# sensing_unit_rev3.net
KiCad netlist of a schematic drawn in EAGLE
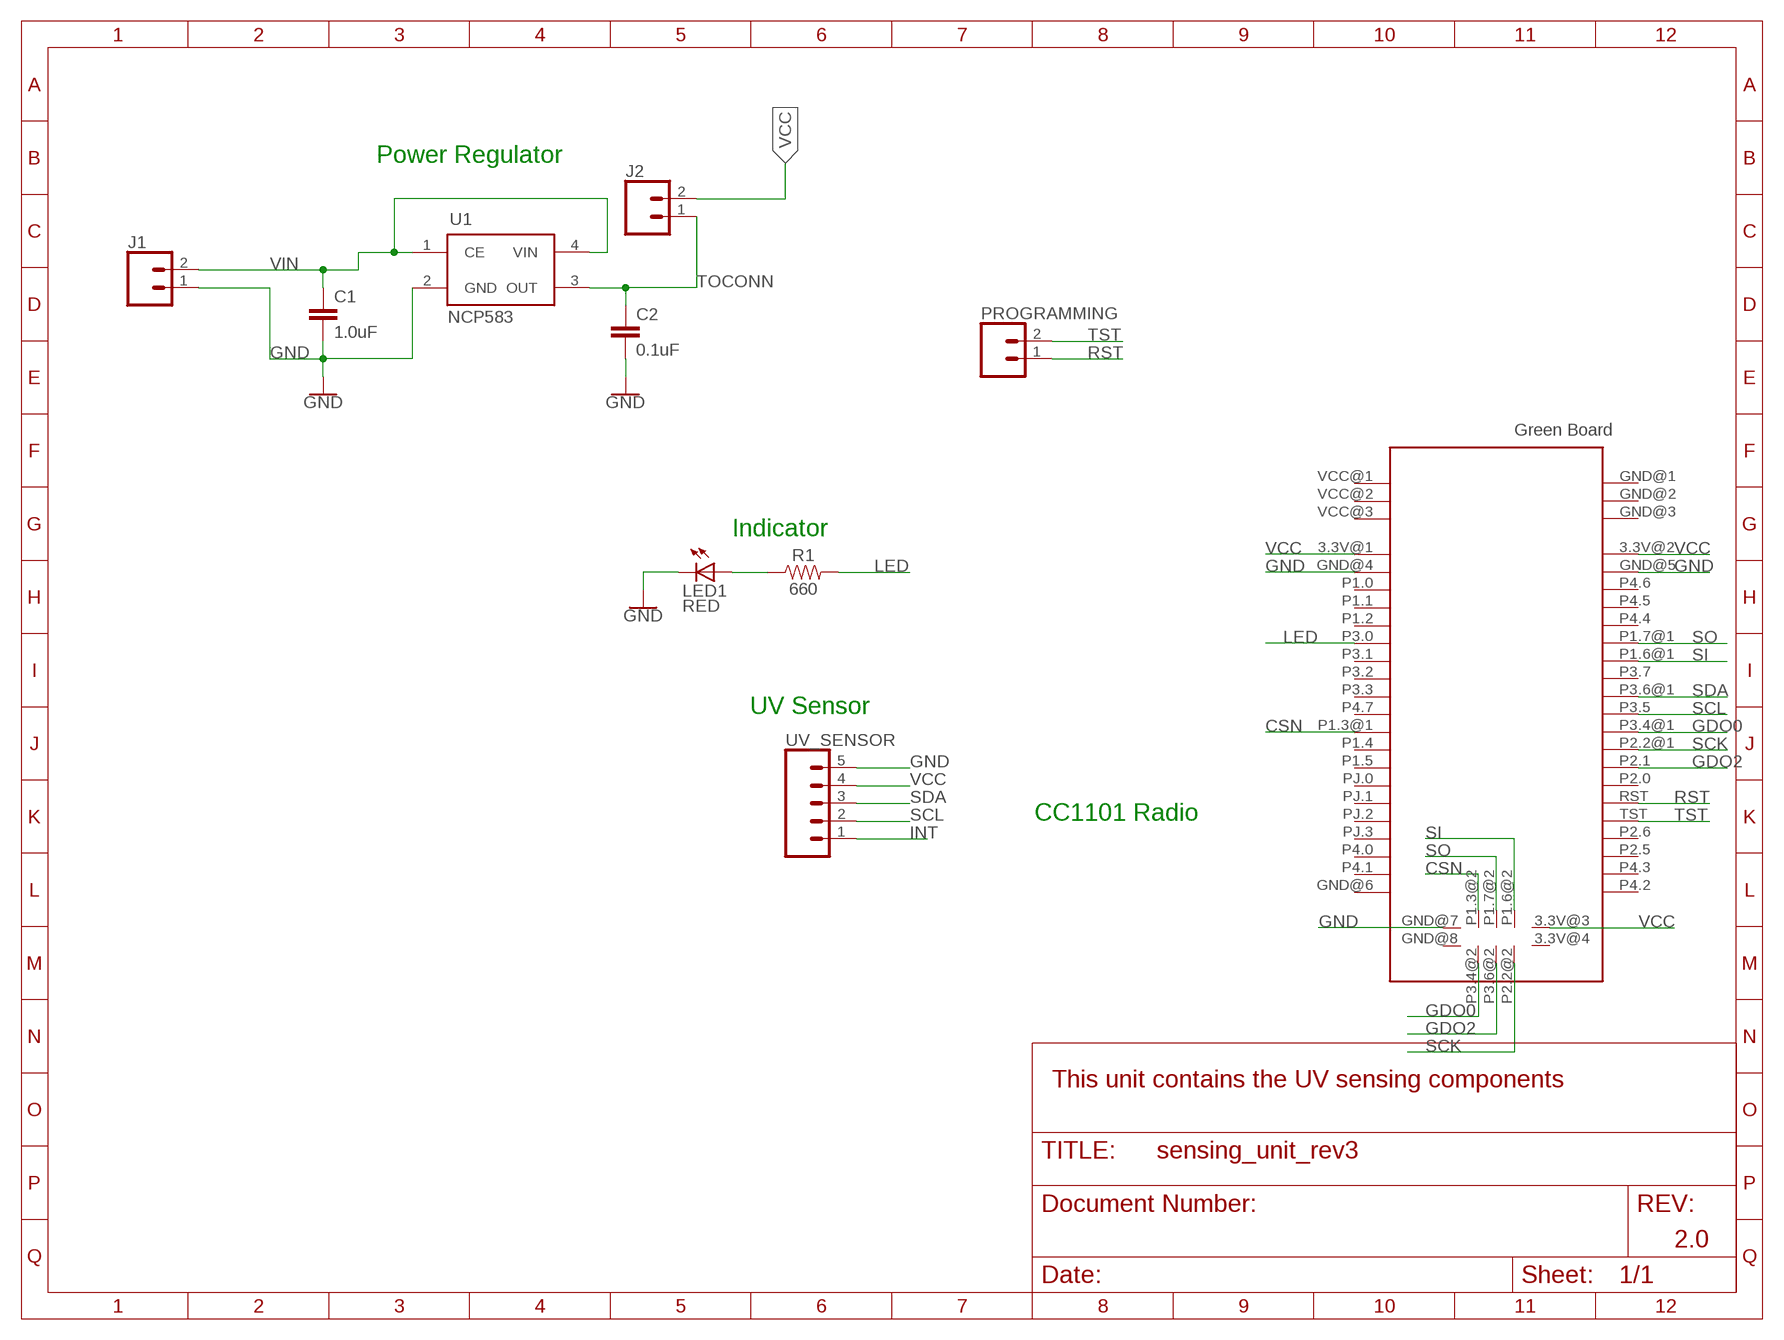
[diagram p0: schematic, sheet 1]

(export (version "E")
  (design (tool "Eeschema 10.0.6"))
  (components
    (comp (ref "C1")
      (value "1.0uF")
      (footprint "eagle-import:0805")
      (libsource (lib "eagle-import") (part "1.0UF-0805-25V-(+80/-20%)"))
    )
    (comp (ref "C2")
      (value "0.1uF")
      (footprint "eagle-import:0805")
      (libsource (lib "eagle-import") (part "1.0UF-0805-25V-(+80/-20%)"))
    )
    (comp (ref "J1")
      (value "CONN_02")
      (footprint "eagle-import:1X02")
      (libsource (lib "eagle-import") (part "CONN_02"))
    )
    (comp (ref "J2")
      (value "CONN_02")
      (footprint "eagle-import:1X02")
      (libsource (lib "eagle-import") (part "CONN_02"))
    )
    (comp (ref "LED1")
      (value "RED")
      (footprint "eagle-import:CHIP-LED0805")
      (libsource (lib "eagle-import") (part "LEDCHIP-LED0805"))
    )
    (comp (ref "PROGRAMMING")
      (value "CONN_02")
      (footprint "eagle-import:1X02")
      (libsource (lib "eagle-import") (part "SparkFun-Connectors_513_CONN_02"))
    )
    (comp (ref "R1")
      (value "660")
      (footprint "eagle-import:0805")
      (libsource (lib "eagle-import") (part "RESISTOR0805"))
    )
    (comp (ref "U$1")
      (value "GREEDNBRD")
      (footprint "eagle-import:GREENBRD")
      (libsource (lib "eagle-import") (part "GREEDNBRD"))
    )
    (comp (ref "U1")
      (value "NCP583")
      (footprint "eagle-import:SC82-AB_1PRIMARY")
      (libsource (lib "eagle-import") (part "NCP583"))
    )
    (comp (ref "UV_SENSOR")
      (value "CONN_05")
      (footprint "eagle-import:1X05")
      (libsource (lib "eagle-import") (part "CONN_05"))
    )
  )
  (nets
    (net (code "1") (name "/CSN") (class "Default")
      (node (ref "U$1") (pin "P1.3@1") (pinfunction "P1.3_P1.3@1") (pintype "bidirectional"))
      (node (ref "U$1") (pin "P1.3@2") (pinfunction "P1.3_P1.3@2") (pintype "bidirectional"))
    )
    (net (code "2") (name "/GDO0") (class "Default")
      (node (ref "U$1") (pin "P3.4@1") (pinfunction "P3.4_P3.4@1") (pintype "bidirectional"))
      (node (ref "U$1") (pin "P3.4@2") (pinfunction "P3.4_P3.4@2") (pintype "bidirectional"))
    )
    (net (code "3") (name "/GDO2") (class "Default")
      (node (ref "U$1") (pin "P2.1") (pinfunction "P2.1_P2.1") (pintype "bidirectional"))
      (node (ref "U$1") (pin "P3.6@2") (pinfunction "P3.6_P3.6@2") (pintype "bidirectional"))
    )
    (net (code "4") (name "/INT") (class "Default")
      (node (ref "UV_SENSOR") (pin "1") (pinfunction "1_1") (pintype "passive"))
    )
    (net (code "5") (name "/LED") (class "Default")
      (node (ref "R1") (pin "2") (pinfunction "2_2") (pintype "passive"))
      (node (ref "U$1") (pin "P3.0") (pinfunction "P3.0_P3.0") (pintype "bidirectional"))
    )
    (net (code "6") (name "/RST") (class "Default")
      (node (ref "PROGRAMMING") (pin "1") (pinfunction "1_1") (pintype "passive"))
      (node (ref "U$1") (pin "RST") (pinfunction "RST_RST") (pintype "bidirectional"))
    )
    (net (code "7") (name "/SCK") (class "Default")
      (node (ref "U$1") (pin "P2.2@1") (pinfunction "P2.2_P2.2@1") (pintype "bidirectional"))
      (node (ref "U$1") (pin "P2.2@2") (pinfunction "P2.2_P2.2@2") (pintype "bidirectional"))
    )
    (net (code "8") (name "/SCL") (class "Default")
      (node (ref "U$1") (pin "P3.5") (pinfunction "P3.5_P3.5") (pintype "bidirectional"))
      (node (ref "UV_SENSOR") (pin "2") (pinfunction "2_2") (pintype "passive"))
    )
    (net (code "9") (name "/SDA") (class "Default")
      (node (ref "U$1") (pin "P3.6@1") (pinfunction "P3.6_P3.6@1") (pintype "bidirectional"))
      (node (ref "UV_SENSOR") (pin "3") (pinfunction "3_3") (pintype "passive"))
    )
    (net (code "10") (name "/SI") (class "Default")
      (node (ref "U$1") (pin "P1.6@1") (pinfunction "P1.6_P1.6@1") (pintype "bidirectional"))
      (node (ref "U$1") (pin "P1.6@2") (pinfunction "P1.6_P1.6@2") (pintype "bidirectional"))
    )
    (net (code "11") (name "/SO") (class "Default")
      (node (ref "U$1") (pin "P1.7@1") (pinfunction "P1.7_P1.7@1") (pintype "bidirectional"))
      (node (ref "U$1") (pin "P1.7@2") (pinfunction "P1.7_P1.7@2") (pintype "bidirectional"))
    )
    (net (code "12") (name "/TOCONN") (class "Default")
      (node (ref "C2") (pin "1") (pinfunction "1_1") (pintype "passive"))
      (node (ref "J2") (pin "1") (pinfunction "1_1") (pintype "passive"))
      (node (ref "U1") (pin "3") (pinfunction "OUT_3") (pintype "bidirectional"))
    )
    (net (code "13") (name "/TST") (class "Default")
      (node (ref "PROGRAMMING") (pin "2") (pinfunction "2_2") (pintype "passive"))
      (node (ref "U$1") (pin "TST") (pinfunction "TST_TST") (pintype "bidirectional"))
    )
    (net (code "14") (name "/VIN") (class "Default")
      (node (ref "C1") (pin "1") (pinfunction "1_1") (pintype "passive"))
      (node (ref "J1") (pin "2") (pinfunction "2_2") (pintype "passive"))
      (node (ref "U1") (pin "1") (pinfunction "CE_1") (pintype "bidirectional"))
      (node (ref "U1") (pin "4") (pinfunction "VIN_4") (pintype "bidirectional"))
    )
    (net (code "15") (name "GND") (class "Default")
      (node (ref "C1") (pin "2") (pinfunction "2_2") (pintype "passive"))
      (node (ref "C2") (pin "2") (pinfunction "2_2") (pintype "passive"))
      (node (ref "J1") (pin "1") (pinfunction "1_1") (pintype "passive"))
      (node (ref "LED1") (pin "C") (pinfunction "C_C") (pintype "passive"))
      (node (ref "U$1") (pin "GND@4") (pinfunction "GND_GND@4") (pintype "bidirectional"))
      (node (ref "U$1") (pin "GND@5") (pinfunction "GND_GND@5") (pintype "bidirectional"))
      (node (ref "U$1") (pin "GND@7") (pinfunction "GND_GND@7") (pintype "bidirectional"))
      (node (ref "U1") (pin "2") (pinfunction "GND_2") (pintype "bidirectional"))
      (node (ref "UV_SENSOR") (pin "5") (pinfunction "5_5") (pintype "passive"))
    )
    (net (code "16") (name "Net-(LED1-PadA)") (class "Default")
      (node (ref "LED1") (pin "A") (pinfunction "A_A") (pintype "passive"))
      (node (ref "R1") (pin "1") (pinfunction "1_1") (pintype "passive"))
    )
    (net (code "17") (name "VCC") (class "Default")
      (node (ref "J2") (pin "2") (pinfunction "2_2") (pintype "passive"))
      (node (ref "U$1") (pin "3.3V@1") (pinfunction "3.3V_3.3V@1") (pintype "bidirectional"))
      (node (ref "U$1") (pin "3.3V@2") (pinfunction "3.3V_3.3V@2") (pintype "bidirectional"))
      (node (ref "U$1") (pin "3.3V@3") (pinfunction "3.3V_3.3V@3") (pintype "bidirectional"))
      (node (ref "UV_SENSOR") (pin "4") (pinfunction "4_4") (pintype "passive"))
    )
    (net (code "18") (name "unconnected-(U$1-3.3V-Pad3.3V@4)") (class "Default")
      (node (ref "U$1") (pin "3.3V@4") (pinfunction "3.3V_3.3V@4") (pintype "bidirectional"))
    )
    (net (code "19") (name "unconnected-(U$1-GND-PadGND@1)") (class "Default")
      (node (ref "U$1") (pin "GND@1") (pinfunction "GND_GND@1") (pintype "bidirectional"))
    )
    (net (code "20") (name "unconnected-(U$1-GND-PadGND@2)") (class "Default")
      (node (ref "U$1") (pin "GND@2") (pinfunction "GND_GND@2") (pintype "bidirectional"))
    )
    (net (code "21") (name "unconnected-(U$1-GND-PadGND@3)") (class "Default")
      (node (ref "U$1") (pin "GND@3") (pinfunction "GND_GND@3") (pintype "bidirectional"))
    )
    (net (code "22") (name "unconnected-(U$1-GND-PadGND@6)") (class "Default")
      (node (ref "U$1") (pin "GND@6") (pinfunction "GND_GND@6") (pintype "bidirectional"))
    )
    (net (code "23") (name "unconnected-(U$1-GND-PadGND@8)") (class "Default")
      (node (ref "U$1") (pin "GND@8") (pinfunction "GND_GND@8") (pintype "bidirectional"))
    )
    (net (code "24") (name "unconnected-(U$1-PadP1.0)") (class "Default")
      (node (ref "U$1") (pin "P1.0") (pinfunction "P1.0_P1.0") (pintype "bidirectional"))
    )
    (net (code "25") (name "unconnected-(U$1-PadP1.1)") (class "Default")
      (node (ref "U$1") (pin "P1.1") (pinfunction "P1.1_P1.1") (pintype "bidirectional"))
    )
    (net (code "26") (name "unconnected-(U$1-PadP1.2)") (class "Default")
      (node (ref "U$1") (pin "P1.2") (pinfunction "P1.2_P1.2") (pintype "bidirectional"))
    )
    (net (code "27") (name "unconnected-(U$1-PadP1.4)") (class "Default")
      (node (ref "U$1") (pin "P1.4") (pinfunction "P1.4_P1.4") (pintype "bidirectional"))
    )
    (net (code "28") (name "unconnected-(U$1-PadP1.5)") (class "Default")
      (node (ref "U$1") (pin "P1.5") (pinfunction "P1.5_P1.5") (pintype "bidirectional"))
    )
    (net (code "29") (name "unconnected-(U$1-PadP2.0)") (class "Default")
      (node (ref "U$1") (pin "P2.0") (pinfunction "P2.0_P2.0") (pintype "bidirectional"))
    )
    (net (code "30") (name "unconnected-(U$1-PadP2.5)") (class "Default")
      (node (ref "U$1") (pin "P2.5") (pinfunction "P2.5_P2.5") (pintype "bidirectional"))
    )
    (net (code "31") (name "unconnected-(U$1-PadP2.6)") (class "Default")
      (node (ref "U$1") (pin "P2.6") (pinfunction "P2.6_P2.6") (pintype "bidirectional"))
    )
    (net (code "32") (name "unconnected-(U$1-PadP3.1)") (class "Default")
      (node (ref "U$1") (pin "P3.1") (pinfunction "P3.1_P3.1") (pintype "bidirectional"))
    )
    (net (code "33") (name "unconnected-(U$1-PadP3.2)") (class "Default")
      (node (ref "U$1") (pin "P3.2") (pinfunction "P3.2_P3.2") (pintype "bidirectional"))
    )
    (net (code "34") (name "unconnected-(U$1-PadP3.3)") (class "Default")
      (node (ref "U$1") (pin "P3.3") (pinfunction "P3.3_P3.3") (pintype "bidirectional"))
    )
    (net (code "35") (name "unconnected-(U$1-PadP3.7)") (class "Default")
      (node (ref "U$1") (pin "P3.7") (pinfunction "P3.7_P3.7") (pintype "bidirectional"))
    )
    (net (code "36") (name "unconnected-(U$1-PadP4.0)") (class "Default")
      (node (ref "U$1") (pin "P4.0") (pinfunction "P4.0_P4.0") (pintype "bidirectional"))
    )
    (net (code "37") (name "unconnected-(U$1-PadP4.1)") (class "Default")
      (node (ref "U$1") (pin "P4.1") (pinfunction "P4.1_P4.1") (pintype "bidirectional"))
    )
    (net (code "38") (name "unconnected-(U$1-PadP4.2)") (class "Default")
      (node (ref "U$1") (pin "P4.2") (pinfunction "P4.2_P4.2") (pintype "bidirectional"))
    )
    (net (code "39") (name "unconnected-(U$1-PadP4.3)") (class "Default")
      (node (ref "U$1") (pin "P4.3") (pinfunction "P4.3_P4.3") (pintype "bidirectional"))
    )
    (net (code "40") (name "unconnected-(U$1-PadP4.4)") (class "Default")
      (node (ref "U$1") (pin "P4.4") (pinfunction "P4.4_P4.4") (pintype "bidirectional"))
    )
    (net (code "41") (name "unconnected-(U$1-PadP4.5)") (class "Default")
      (node (ref "U$1") (pin "P4.5") (pinfunction "P4.5_P4.5") (pintype "bidirectional"))
    )
    (net (code "42") (name "unconnected-(U$1-PadP4.6)") (class "Default")
      (node (ref "U$1") (pin "P4.6") (pinfunction "P4.6_P4.6") (pintype "bidirectional"))
    )
    (net (code "43") (name "unconnected-(U$1-PadP4.7)") (class "Default")
      (node (ref "U$1") (pin "P4.7") (pinfunction "P4.7_P4.7") (pintype "bidirectional"))
    )
    (net (code "44") (name "unconnected-(U$1-PadPJ.0)") (class "Default")
      (node (ref "U$1") (pin "PJ.0") (pinfunction "PJ.0_PJ.0") (pintype "bidirectional"))
    )
    (net (code "45") (name "unconnected-(U$1-PadPJ.1)") (class "Default")
      (node (ref "U$1") (pin "PJ.1") (pinfunction "PJ.1_PJ.1") (pintype "bidirectional"))
    )
    (net (code "46") (name "unconnected-(U$1-PadPJ.2)") (class "Default")
      (node (ref "U$1") (pin "PJ.2") (pinfunction "PJ.2_PJ.2") (pintype "bidirectional"))
    )
    (net (code "47") (name "unconnected-(U$1-PadPJ.3)") (class "Default")
      (node (ref "U$1") (pin "PJ.3") (pinfunction "PJ.3_PJ.3") (pintype "bidirectional"))
    )
    (net (code "48") (name "unconnected-(U$1-VCC-PadVCC@1)") (class "Default")
      (node (ref "U$1") (pin "VCC@1") (pinfunction "VCC_VCC@1") (pintype "bidirectional"))
    )
    (net (code "49") (name "unconnected-(U$1-VCC-PadVCC@2)") (class "Default")
      (node (ref "U$1") (pin "VCC@2") (pinfunction "VCC_VCC@2") (pintype "bidirectional"))
    )
    (net (code "50") (name "unconnected-(U$1-VCC-PadVCC@3)") (class "Default")
      (node (ref "U$1") (pin "VCC@3") (pinfunction "VCC_VCC@3") (pintype "bidirectional"))
    )
  )
)
